# main.net
KiCad netlist of a schematic drawn in Altium Designer
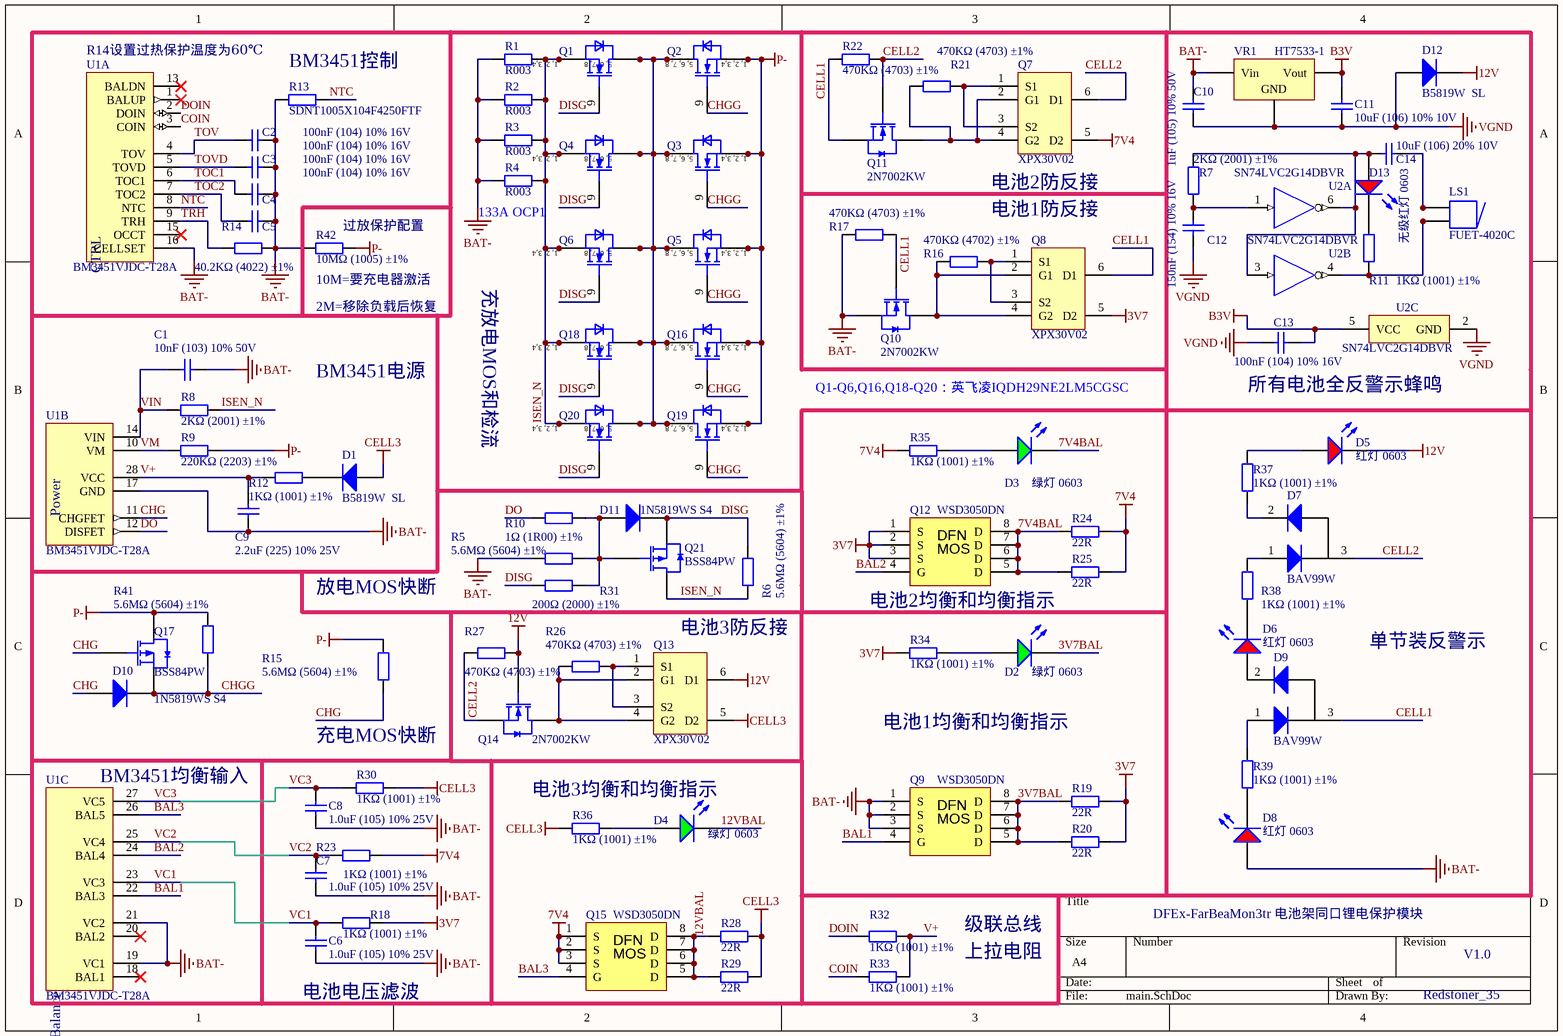
[diagram p0: main.SchDoc]

(export (version "E")
  (design (tool "Eeschema 10.0.6"))
  (components
    (comp (ref "C1")
      (value "10nF (103) 10% 50V")
      (footprint "0402_C")
      (description "贴片电容")
      (libsource (lib "Miscellaneous Devices LC") (part "0402 10nF (103) 10% 50V"))
    )
    (comp (ref "C2")
      (value "100nF (104) 10% 16V")
      (footprint "0402_C")
      (description "贴片电容")
      (libsource (lib "Miscellaneous Devices LC") (part "0402 100nF (104) 10% 16V"))
    )
    (comp (ref "C3")
      (value "100nF (104) 10% 16V")
      (footprint "0402_C")
      (description "贴片电容")
      (libsource (lib "Miscellaneous Devices LC") (part "0402 100nF (104) 10% 16V"))
    )
    (comp (ref "C4")
      (value "100nF (104) 10% 16V")
      (footprint "0402_C")
      (description "贴片电容")
      (libsource (lib "Miscellaneous Devices LC") (part "0402 100nF (104) 10% 16V"))
    )
    (comp (ref "C5")
      (value "100nF (104) 10% 16V")
      (footprint "0402_C")
      (description "贴片电容")
      (libsource (lib "Miscellaneous Devices LC") (part "0402 100nF (104) 10% 16V"))
    )
    (comp (ref "C6")
      (value "1.0uF (105) 10% 25V")
      (footprint "0402_C")
      (description "贴片电容")
      (libsource (lib "Miscellaneous Devices LC") (part "0402 1.0uF (105) 10% 25V"))
    )
    (comp (ref "C7")
      (value "1.0uF (105) 10% 25V")
      (footprint "0402_C")
      (description "贴片电容")
      (libsource (lib "Miscellaneous Devices LC") (part "0402 1.0uF (105) 10% 25V"))
    )
    (comp (ref "C8")
      (value "1.0uF (105) 10% 25V")
      (footprint "0402_C")
      (description "贴片电容")
      (libsource (lib "Miscellaneous Devices LC") (part "0402 1.0uF (105) 10% 25V"))
    )
    (comp (ref "C9")
      (value "2.2uF (225) 10% 25V")
      (footprint "0402_C")
      (description "贴片电容")
      (libsource (lib "Miscellaneous Devices LC") (part "0402 2.2nF (222) 10% 50V"))
    )
    (comp (ref "C10")
      (value "1uF (105) 10% 50V")
      (footprint "0603_C")
      (description "贴片电容")
      (libsource (lib "Miscellaneous Devices LC") (part "0603 1uF (105) 10% 50V"))
    )
    (comp (ref "C11")
      (value "10uF (106) 10% 10V")
      (footprint "0603_C")
      (description "贴片电容")
      (libsource (lib "Miscellaneous Devices LC") (part "0603 10uF (106) 10% 10V"))
    )
    (comp (ref "C12")
      (value "150nF (154) 10% 16V")
      (footprint "0402_C")
      (description "贴片电容")
      (libsource (lib "Miscellaneous Devices LC") (part "0402 100nF (104) 10% 16V"))
    )
    (comp (ref "C13")
      (value "100nF (104) 10% 16V")
      (footprint "0402_C")
      (description "贴片电容")
      (libsource (lib "Miscellaneous Devices LC") (part "0402 100nF (104) 10% 16V"))
    )
    (comp (ref "C14")
      (value "10uF (106) 20% 10V")
      (footprint "0402_C")
      (description "贴片电容")
      (libsource (lib "Miscellaneous Devices LC") (part "0402 10uF (106) 20% 6.3V"))
    )
    (comp (ref "D1")
      (value "B5819W  SL")
      (footprint "SOD-123")
      (description "肖特基二极管")
      (libsource (lib "Miscellaneous Devices LC") (part "SOD-123 B5819W  SL"))
    )
    (comp (ref "D2")
      (value "绿灯 0603")
      (footprint "0603_LED_S1")
      (description "发光二极管")
      (libsource (lib "Miscellaneous Devices LC") (part "0603 绿灯"))
    )
    (comp (ref "D3")
      (value "绿灯 0603")
      (footprint "0603_LED_S1")
      (description "发光二极管")
      (libsource (lib "Miscellaneous Devices LC") (part "0603 绿灯"))
    )
    (comp (ref "D4")
      (value "绿灯 0603")
      (footprint "0603_LED_S1")
      (description "发光二极管")
      (libsource (lib "Miscellaneous Devices LC") (part "0603 绿灯"))
    )
    (comp (ref "D5")
      (value "红灯 0603")
      (footprint "0603_LED_S1")
      (description "发光二极管")
      (libsource (lib "Miscellaneous Devices LC") (part "0603 红灯"))
    )
    (comp (ref "D6")
      (value "红灯 0603")
      (footprint "0603_LED_S1")
      (description "发光二极管")
      (libsource (lib "Miscellaneous Devices LC") (part "0603 红灯"))
    )
    (comp (ref "D7")
      (value "BAV99W")
      (footprint "SC70-3")
      (description "开关二极管")
      (libsource (lib "Miscellaneous Devices LC") (part "SOT-23 BAV99 A7W"))
    )
    (comp (ref "D8")
      (value "红灯 0603")
      (footprint "0603_LED_S1")
      (description "发光二极管")
      (libsource (lib "Miscellaneous Devices LC") (part "0603 红灯"))
    )
    (comp (ref "D9")
      (value "BAV99W")
      (footprint "SC70-3")
      (description "开关二极管")
      (libsource (lib "Miscellaneous Devices LC") (part "SOT-23 BAV99 A7W"))
    )
    (comp (ref "D10")
      (value "1N5819WS S4")
      (footprint "SOD-323")
      (description "二极管")
      (libsource (lib "Miscellaneous Devices LC") (part "SOD-323 1N4148WS T4"))
    )
    (comp (ref "D11")
      (value "1N5819WS S4")
      (footprint "SOD-323")
      (description "二极管")
      (libsource (lib "Miscellaneous Devices LC") (part "SOD-323 1N4148WS T4"))
    )
    (comp (ref "D12")
      (value "B5819W  SL")
      (footprint "SOD-123")
      (description "肖特基二极管")
      (libsource (lib "Miscellaneous Devices LC") (part "SOD-123 B5819W  SL"))
    )
    (comp (ref "D13")
      (value "无级红灯 0603")
      (footprint "0603_LED_S1")
      (description "发光二极管")
      (libsource (lib "Miscellaneous Devices LC") (part "0603 红灯"))
    )
    (comp (ref "LS1")
      (value "FUET-4020C")
      (footprint "FUET-4020C")
      (description "福声科技有限公司侧发声电磁式蜂鸣器，4*4*2mm尺寸")
      (fields (field (name "PUBLISHER") "Altium Limited"))
      (libsource (lib "Miscellaneous Devices") (part "Buzzer"))
    )
    (comp (ref "Q1")
      (value "IQDH29NE2LM5CGSC")
      (footprint "IFX-PG-WHTFN-9-2-V")
      (fields (field (name "MANUFACTURER") "Infineon Technologies"))
      (libsource (lib "custom") (part "IQDH29NE2LM5CGSC"))
    )
    (comp (ref "Q2")
      (value "IQDH29NE2LM5CGSC")
      (footprint "IFX-PG-WHTFN-9-2-V")
      (fields (field (name "MANUFACTURER") "Infineon Technologies"))
      (libsource (lib "custom") (part "IQDH29NE2LM5CGSC"))
    )
    (comp (ref "Q3")
      (value "IQDH29NE2LM5CGSC")
      (footprint "IFX-PG-WHTFN-9-2-V")
      (fields (field (name "MANUFACTURER") "Infineon Technologies"))
      (libsource (lib "custom") (part "IQDH29NE2LM5CGSC"))
    )
    (comp (ref "Q4")
      (value "IQDH29NE2LM5CGSC")
      (footprint "IFX-PG-WHTFN-9-2-V")
      (fields (field (name "MANUFACTURER") "Infineon Technologies"))
      (libsource (lib "custom") (part "IQDH29NE2LM5CGSC"))
    )
    (comp (ref "Q5")
      (value "IQDH29NE2LM5CGSC")
      (footprint "IFX-PG-WHTFN-9-2-V")
      (fields (field (name "MANUFACTURER") "Infineon Technologies"))
      (libsource (lib "custom") (part "IQDH29NE2LM5CGSC"))
    )
    (comp (ref "Q6")
      (value "IQDH29NE2LM5CGSC")
      (footprint "IFX-PG-WHTFN-9-2-V")
      (fields (field (name "MANUFACTURER") "Infineon Technologies"))
      (libsource (lib "custom") (part "IQDH29NE2LM5CGSC"))
    )
    (comp (ref "Q7")
      (value "XPX30V02")
      (footprint "EDFN3x3")
      (description "双N沟道MOSFET, DFN3x3 30V 40A 10mΩ")
      (libsource (lib "custom") (part "XPX10H03RX"))
    )
    (comp (ref "Q8")
      (value "XPX30V02")
      (footprint "EDFN3x3")
      (description "双N沟道MOSFET, DFN3x3 30V 40A 10mΩ")
      (libsource (lib "custom") (part "XPX10H03RX"))
    )
    (comp (ref "Q9")
      (value "WSD3050DN")
      (footprint "DFN-8_L3.0-W3.0-P0.65-BL")
      (description "PDFN3x3 20V 50A 5.8mΩ N-Ch MOSFET")
      (libsource (lib "custom") (part "SON/DFN5x6 MOS"))
    )
    (comp (ref "Q10")
      (value "2N7002KW")
      (footprint "SC70-3")
      (description "单N沟道MOSFET(场效应管)")
      (libsource (lib "Miscellaneous Devices LC") (part "2N7002 7002"))
    )
    (comp (ref "Q11")
      (value "2N7002KW")
      (footprint "SC70-3")
      (description "单N沟道MOSFET(场效应管)")
      (libsource (lib "Miscellaneous Devices LC") (part "2N7002 7002"))
    )
    (comp (ref "Q12")
      (value "WSD3050DN")
      (footprint "DFN-8_L3.0-W3.0-P0.65-BL")
      (description "PDFN3x3 20V 50A 5.8mΩ N-Ch MOSFET")
      (libsource (lib "custom") (part "SON/DFN5x6 MOS"))
    )
    (comp (ref "Q13")
      (value "XPX30V02")
      (footprint "EDFN3x3")
      (description "双N沟道MOSFET, DFN3x3 30V 40A 10mΩ")
      (libsource (lib "custom") (part "XPX10H03RX"))
    )
    (comp (ref "Q14")
      (value "2N7002KW")
      (footprint "SC70-3")
      (description "单N沟道MOSFET(场效应管)")
      (libsource (lib "Miscellaneous Devices LC") (part "2N7002 7002"))
    )
    (comp (ref "Q15")
      (value "WSD3050DN")
      (footprint "DFN-8_L3.0-W3.0-P0.65-BL")
      (description "PDFN3x3 20V 50A 5.8mΩ N-Ch MOSFET")
      (libsource (lib "custom") (part "SON/DFN5x6 MOS"))
    )
    (comp (ref "Q16")
      (value "IQDH29NE2LM5CGSC")
      (footprint "IFX-PG-WHTFN-9-2-V")
      (fields (field (name "MANUFACTURER") "Infineon Technologies"))
      (libsource (lib "custom") (part "IQDH29NE2LM5CGSC"))
    )
    (comp (ref "Q17")
      (value "BSS84PW")
      (footprint "SC70-3")
      (description "MOS(场效应管)")
      (libsource (lib "Miscellaneous Devices LC") (part "SI2301CDS-T1-GE3"))
    )
    (comp (ref "Q18")
      (value "IQDH29NE2LM5CGSC")
      (footprint "IFX-PG-WHTFN-9-2-V")
      (fields (field (name "MANUFACTURER") "Infineon Technologies"))
      (libsource (lib "custom") (part "IQDH29NE2LM5CGSC"))
    )
    (comp (ref "Q19")
      (value "IQDH29NE2LM5CGSC")
      (footprint "IFX-PG-WHTFN-9-2-V")
      (fields (field (name "MANUFACTURER") "Infineon Technologies"))
      (libsource (lib "custom") (part "IQDH29NE2LM5CGSC"))
    )
    (comp (ref "Q20")
      (value "IQDH29NE2LM5CGSC")
      (footprint "IFX-PG-WHTFN-9-2-V")
      (fields (field (name "MANUFACTURER") "Infineon Technologies"))
      (libsource (lib "custom") (part "IQDH29NE2LM5CGSC"))
    )
    (comp (ref "Q21")
      (value "BSS84PW")
      (footprint "SC70-3")
      (description "MOS(场效应管)")
      (libsource (lib "Miscellaneous Devices LC") (part "SI2301CDS-T1-GE3"))
    )
    (comp (ref "R1")
      (value "R003")
      (footprint "2512")
      (description "2512尺寸 3W 3mΩ ±1% 合金检流电阻")
      (fields (field (name "PUBLISHER") "Altium Limited"))
      (libsource (lib "山猫的集成库20190318") (part "Res"))
    )
    (comp (ref "R2")
      (value "R003")
      (footprint "2512")
      (description "2512尺寸 3W 3mΩ ±1% 合金检流电阻")
      (fields (field (name "PUBLISHER") "Altium Limited"))
      (libsource (lib "山猫的集成库20190318") (part "Res"))
    )
    (comp (ref "R3")
      (value "R003")
      (footprint "2512")
      (description "2512尺寸 3W 3mΩ ±1% 合金检流电阻")
      (fields (field (name "PUBLISHER") "Altium Limited"))
      (libsource (lib "山猫的集成库20190318") (part "Res"))
    )
    (comp (ref "R4")
      (value "R003")
      (footprint "2512")
      (description "2512尺寸 3W 3mΩ ±1% 合金检流电阻")
      (fields (field (name "PUBLISHER") "Altium Limited"))
      (libsource (lib "山猫的集成库20190318") (part "Res"))
    )
    (comp (ref "R5")
      (value "5.6MΩ (5604) ±1%")
      (footprint "0402_R")
      (description "贴片电阻")
      (libsource (lib "Miscellaneous Devices LC") (part "0402 1MΩ (1004) 1%"))
    )
    (comp (ref "R6")
      (value "5.6MΩ (5604) ±1%")
      (footprint "0402_R")
      (description "贴片电阻")
      (libsource (lib "") (part "0402 1MΩ (1004) 1%_1"))
    )
    (comp (ref "R7")
      (value "2KΩ (2001) ±1%")
      (footprint "0402_R")
      (description "贴片电阻")
      (libsource (lib "") (part "0402 1KΩ (1001) 1%_1"))
    )
    (comp (ref "R8")
      (value "2KΩ (2001) ±1%")
      (footprint "0402_R")
      (description "贴片电阻")
      (libsource (lib "Miscellaneous Devices LC") (part "0402 2KΩ (2001) 1%"))
    )
    (comp (ref "R9")
      (value "220KΩ (2203) ±1%")
      (footprint "0402_R")
      (description "贴片电阻")
      (libsource (lib "Miscellaneous Devices LC") (part "0402 220KΩ (2203) 1%"))
    )
    (comp (ref "R10")
      (value "1Ω (1R00) ±1%")
      (footprint "0402_R")
      (description "贴片电阻")
      (libsource (lib "Miscellaneous Devices LC") (part "0402 1Ω (1R00) 1%"))
    )
    (comp (ref "R11")
      (value "1KΩ (1001) ±1%")
      (footprint "0402_R")
      (description "贴片电阻")
      (libsource (lib "") (part "0402 1KΩ (1001) 1%_1"))
    )
    (comp (ref "R12")
      (value "1KΩ (1001) ±1%")
      (footprint "0805_R")
      (description "贴片电阻")
      (libsource (lib "Miscellaneous Devices LC") (part "0805 1KΩ (1001) 1%"))
    )
    (comp (ref "R13")
      (value "SDNT1005X104F4250FTF")
      (footprint "0402_R")
      (description "贴片NTC热敏电阻 100KΩ (1003) ±1% B4250")
      (libsource (lib "Miscellaneous Devices LC") (part "0402 100KΩ (1003) 1%"))
    )
    (comp (ref "R14")
      (value "40.2KΩ (4022) ±1%")
      (footprint "0402_R")
      (description "贴片电阻")
      (libsource (lib "Miscellaneous Devices LC") (part "0402 56KΩ (5602) 1%"))
    )
    (comp (ref "R15")
      (value "5.6MΩ (5604) ±1%")
      (footprint "0402_R")
      (description "贴片电阻")
      (libsource (lib "") (part "0402 1MΩ (1004) 1%_1"))
    )
    (comp (ref "R16")
      (value "470KΩ (4702) ±1%")
      (footprint "0402_R")
      (description "贴片电阻")
      (libsource (lib "Miscellaneous Devices LC") (part "0402 20KΩ (2002) 1%"))
    )
    (comp (ref "R17")
      (value "470KΩ (4703) ±1%")
      (footprint "0402_R")
      (description "贴片电阻")
      (libsource (lib "Miscellaneous Devices LC") (part "0402 470KΩ (4703) 1%"))
    )
    (comp (ref "R18")
      (value "1KΩ (1001) ±1%")
      (footprint "0402_R")
      (description "贴片电阻")
      (libsource (lib "Miscellaneous Devices LC") (part "0402 1KΩ (1001) 1%"))
    )
    (comp (ref "R19")
      (value "22R")
      (footprint "1210R")
      (description "Resistor")
      (fields (field (name "PUBLISHER") "Altium Limited"))
      (libsource (lib "山猫的集成库20190318") (part "Res"))
    )
    (comp (ref "R20")
      (value "22R")
      (footprint "1210R")
      (description "Resistor")
      (fields (field (name "PUBLISHER") "Altium Limited"))
      (libsource (lib "山猫的集成库20190318") (part "Res"))
    )
    (comp (ref "R21")
      (value "470KΩ (4703) ±1%")
      (footprint "0402_R")
      (description "贴片电阻")
      (libsource (lib "Miscellaneous Devices LC") (part "0402 470KΩ (4703) 1%"))
    )
    (comp (ref "R22")
      (value "470KΩ (4703) ±1%")
      (footprint "0402_R")
      (description "贴片电阻")
      (libsource (lib "Miscellaneous Devices LC") (part "0402 470KΩ (4703) 1%"))
    )
    (comp (ref "R23")
      (value "1KΩ (1001) ±1%")
      (footprint "0402_R")
      (description "贴片电阻")
      (libsource (lib "Miscellaneous Devices LC") (part "0402 1KΩ (1001) 1%"))
    )
    (comp (ref "R24")
      (value "22R")
      (footprint "1210R")
      (description "Resistor")
      (fields (field (name "PUBLISHER") "Altium Limited"))
      (libsource (lib "山猫的集成库20190318") (part "Res"))
    )
    (comp (ref "R25")
      (value "22R")
      (footprint "1210R")
      (description "Resistor")
      (fields (field (name "PUBLISHER") "Altium Limited"))
      (libsource (lib "山猫的集成库20190318") (part "Res"))
    )
    (comp (ref "R26")
      (value "470KΩ (4703) ±1%")
      (footprint "0402_R")
      (description "贴片电阻")
      (libsource (lib "Miscellaneous Devices LC") (part "0402 470KΩ (4703) 1%"))
    )
    (comp (ref "R27")
      (value "470KΩ (4703) ±1%")
      (footprint "0402_R")
      (description "贴片电阻")
      (libsource (lib "Miscellaneous Devices LC") (part "0402 470KΩ (4703) 1%"))
    )
    (comp (ref "R28")
      (value "22R")
      (footprint "1210R")
      (description "Resistor")
      (fields (field (name "PUBLISHER") "Altium Limited"))
      (libsource (lib "山猫的集成库20190318") (part "Res"))
    )
    (comp (ref "R29")
      (value "22R")
      (footprint "1210R")
      (description "Resistor")
      (fields (field (name "PUBLISHER") "Altium Limited"))
      (libsource (lib "山猫的集成库20190318") (part "Res"))
    )
    (comp (ref "R30")
      (value "1KΩ (1001) ±1%")
      (footprint "0402_R")
      (description "贴片电阻")
      (libsource (lib "Miscellaneous Devices LC") (part "0402 1KΩ (1001) 1%"))
    )
    (comp (ref "R31")
      (value "200Ω (2000) ±1%")
      (footprint "0402_R")
      (description "贴片电阻")
      (libsource (lib "Miscellaneous Devices LC") (part "0402 200Ω (2000) 1%"))
    )
    (comp (ref "R32")
      (value "1KΩ (1001) ±1%")
      (footprint "0402_R")
      (description "贴片电阻")
      (libsource (lib "Miscellaneous Devices LC") (part "0402 1KΩ (1001) 1%"))
    )
    (comp (ref "R33")
      (value "1KΩ (1001) ±1%")
      (footprint "0402_R")
      (description "贴片电阻")
      (libsource (lib "Miscellaneous Devices LC") (part "0402 1KΩ (1001) 1%"))
    )
    (comp (ref "R34")
      (value "1KΩ (1001) ±1%")
      (footprint "0402_R")
      (description "贴片电阻")
      (libsource (lib "Miscellaneous Devices LC") (part "0402 1KΩ (1001) 1%"))
    )
    (comp (ref "R35")
      (value "1KΩ (1001) ±1%")
      (footprint "0402_R")
      (description "贴片电阻")
      (libsource (lib "Miscellaneous Devices LC") (part "0402 1KΩ (1001) 1%"))
    )
    (comp (ref "R36")
      (value "1KΩ (1001) ±1%")
      (footprint "0402_R")
      (description "贴片电阻")
      (libsource (lib "Miscellaneous Devices LC") (part "0402 1KΩ (1001) 1%"))
    )
    (comp (ref "R37")
      (value "1KΩ (1001) ±1%")
      (footprint "0402_R")
      (description "贴片电阻")
      (libsource (lib "") (part "0402 1KΩ (1001) 1%_1"))
    )
    (comp (ref "R38")
      (value "1KΩ (1001) ±1%")
      (footprint "0402_R")
      (description "贴片电阻")
      (libsource (lib "") (part "0402 1KΩ (1001) 1%_1"))
    )
    (comp (ref "R39")
      (value "1KΩ (1001) ±1%")
      (footprint "0402_R")
      (description "贴片电阻")
      (libsource (lib "") (part "0402 1KΩ (1001) 1%_1"))
    )
    (comp (ref "R41")
      (value "5.6MΩ (5604) ±1%")
      (footprint "0402_R")
      (description "贴片电阻")
      (libsource (lib "") (part "0402 1MΩ (1004) 1%_1"))
    )
    (comp (ref "R42")
      (value "10MΩ (1005) ±1%")
      (footprint "0402_R")
      (description "贴片电阻")
      (libsource (lib "Miscellaneous Devices LC") (part "0402 10MΩ (1005) 1%"))
    )
    (comp (ref "U1")
      (value "BM3451VJDC-T28A")
      (footprint "TSSOP28-BM3451")
      (description "2-5串全功能锂电池保护IC，支持级联功能")
      (libsource (lib "custom") (part "BM3451-T28A"))
    )
    (comp (ref "U2")
      (value "SN74LVC2G14DBVR")
      (footprint "DBV0006A_N")
      (description "Dual Schmitt-Trigger Inverter, DBV0006A, LARGE T&R")
      (fields
        (field (name "GENERIC PART NUMBER") "SN74LVC2G14")
        (field (name "MANUFACTURER") "Texas Instruments")
      )
      (libsource (lib "TI_Logic_Little_Logic") (part "SN74LVC2G14DBVR"))
    )
    (comp (ref "VR1")
      (value "HT7533-1")
      (footprint "SOT-89(SOT-89-3)")
      (description "低压差线性稳压(LDO)")
      (libsource (lib "Miscellaneous Devices LC") (part "SOT-89 HT7533-1"))
    )
  )
  (nets
    (net (code "1") (name "/3V7BAL") (class "Default")
      (node (ref "D2") (pin "K") (pinfunction "K_K") (pintype "passive"))
      (node (ref "Q9") (pin "5") (pinfunction "D_5") (pintype "passive"))
      (node (ref "Q9") (pin "6") (pinfunction "D_6") (pintype "passive"))
      (node (ref "Q9") (pin "7") (pinfunction "D_7") (pintype "passive"))
      (node (ref "Q9") (pin "8") (pinfunction "D_8") (pintype "passive"))
      (node (ref "R19") (pin "2") (pinfunction "2_2") (pintype "passive"))
      (node (ref "R20") (pin "2") (pinfunction "2_2") (pintype "passive"))
    )
    (net (code "2") (name "/7V4BAL") (class "Default")
      (node (ref "D3") (pin "K") (pinfunction "K_K") (pintype "passive"))
      (node (ref "Q12") (pin "5") (pinfunction "D_5") (pintype "passive"))
      (node (ref "Q12") (pin "6") (pinfunction "D_6") (pintype "passive"))
      (node (ref "Q12") (pin "7") (pinfunction "D_7") (pintype "passive"))
      (node (ref "Q12") (pin "8") (pinfunction "D_8") (pintype "passive"))
      (node (ref "R24") (pin "2") (pinfunction "2_2") (pintype "passive"))
      (node (ref "R25") (pin "2") (pinfunction "2_2") (pintype "passive"))
    )
    (net (code "3") (name "/12VBAL") (class "Default")
      (node (ref "D4") (pin "K") (pinfunction "K_K") (pintype "passive"))
      (node (ref "Q15") (pin "5") (pinfunction "D_5") (pintype "passive"))
      (node (ref "Q15") (pin "6") (pinfunction "D_6") (pintype "passive"))
      (node (ref "Q15") (pin "7") (pinfunction "D_7") (pintype "passive"))
      (node (ref "Q15") (pin "8") (pinfunction "D_8") (pintype "passive"))
      (node (ref "R28") (pin "2") (pinfunction "2_2") (pintype "passive"))
      (node (ref "R29") (pin "2") (pinfunction "2_2") (pintype "passive"))
    )
    (net (code "4") (name "/BAL1") (class "Default")
      (node (ref "Q9") (pin "4") (pinfunction "G_4") (pintype "passive"))
      (node (ref "U1") (pin "22") (pinfunction "BAL3_22") (pintype "power_in"))
    )
    (net (code "5") (name "/BAL2") (class "Default")
      (node (ref "Q12") (pin "4") (pinfunction "G_4") (pintype "passive"))
      (node (ref "U1") (pin "24") (pinfunction "BAL4_24") (pintype "power_in"))
    )
    (net (code "6") (name "/BAL3") (class "Default")
      (node (ref "Q15") (pin "4") (pinfunction "G_4") (pintype "passive"))
      (node (ref "U1") (pin "26") (pinfunction "BAL5_26") (pintype "power_in"))
    )
    (net (code "7") (name "/CELL1") (class "Default")
      (node (ref "D9") (pin "3") (pinfunction "K_3") (pintype "passive"))
      (node (ref "Q10") (pin "1") (pinfunction "G_1") (pintype "passive"))
      (node (ref "Q11") (pin "2") (pinfunction "S_2") (pintype "passive"))
      (node (ref "Q8") (pin "6") (pinfunction "D1_6") (pintype "passive"))
      (node (ref "R17") (pin "2") (pinfunction "2_2") (pintype "passive"))
      (node (ref "R22") (pin "1") (pinfunction "1_1") (pintype "passive"))
    )
    (net (code "8") (name "/CELL2") (class "Default")
      (node (ref "D7") (pin "3") (pinfunction "K_3") (pintype "passive"))
      (node (ref "Q11") (pin "1") (pinfunction "G_1") (pintype "passive"))
      (node (ref "Q14") (pin "2") (pinfunction "S_2") (pintype "passive"))
      (node (ref "Q7") (pin "6") (pinfunction "D1_6") (pintype "passive"))
      (node (ref "R22") (pin "2") (pinfunction "2_2") (pintype "passive"))
      (node (ref "R27") (pin "1") (pinfunction "1_1") (pintype "passive"))
    )
    (net (code "9") (name "/CHG") (class "Default")
      (node (ref "D10") (pin "1") (pinfunction "A_1") (pintype "passive"))
      (node (ref "Q17") (pin "1") (pinfunction "G_1") (pintype "passive"))
      (node (ref "R15") (pin "1") (pinfunction "1_1") (pintype "passive"))
      (node (ref "U1") (pin "11") (pinfunction "CHGFET_11") (pintype "output"))
    )
    (net (code "10") (name "/CHGG") (class "Default")
      (node (ref "D10") (pin "2") (pinfunction "K_2") (pintype "passive"))
      (node (ref "Q16") (pin "9") (pinfunction "GATE_9") (pintype "passive"))
      (node (ref "Q17") (pin "2") (pinfunction "S_2") (pintype "passive"))
      (node (ref "Q19") (pin "9") (pinfunction "GATE_9") (pintype "passive"))
      (node (ref "Q2") (pin "9") (pinfunction "GATE_9") (pintype "passive"))
      (node (ref "Q3") (pin "9") (pinfunction "GATE_9") (pintype "passive"))
      (node (ref "Q5") (pin "9") (pinfunction "GATE_9") (pintype "passive"))
      (node (ref "R41") (pin "1") (pinfunction "1_1") (pintype "passive"))
    )
    (net (code "11") (name "/COIN") (class "Default")
      (node (ref "R33") (pin "1") (pinfunction "1_1") (pintype "passive"))
      (node (ref "U1") (pin "3") (pinfunction "COIN_3") (pintype "bidirectional"))
    )
    (net (code "12") (name "/DISG") (class "Default")
      (node (ref "D11") (pin "2") (pinfunction "K_2") (pintype "passive"))
      (node (ref "Q1") (pin "9") (pinfunction "GATE_9") (pintype "passive"))
      (node (ref "Q18") (pin "9") (pinfunction "GATE_9") (pintype "passive"))
      (node (ref "Q20") (pin "9") (pinfunction "GATE_9") (pintype "passive"))
      (node (ref "Q21") (pin "2") (pinfunction "S_2") (pintype "passive"))
      (node (ref "Q4") (pin "9") (pinfunction "GATE_9") (pintype "passive"))
      (node (ref "Q6") (pin "9") (pinfunction "GATE_9") (pintype "passive"))
      (node (ref "R31") (pin "1") (pinfunction "1_1") (pintype "passive"))
      (node (ref "R6") (pin "2") (pinfunction "2_2") (pintype "passive"))
    )
    (net (code "13") (name "/DO") (class "Default")
      (node (ref "R10") (pin "1") (pinfunction "1_1") (pintype "passive"))
      (node (ref "U1") (pin "12") (pinfunction "DISFET_12") (pintype "output"))
    )
    (net (code "14") (name "/DOIN") (class "Default")
      (node (ref "R32") (pin "1") (pinfunction "1_1") (pintype "passive"))
      (node (ref "U1") (pin "2") (pinfunction "DOIN_2") (pintype "bidirectional"))
    )
    (net (code "15") (name "/ISEN_N") (class "Default")
      (node (ref "Q1") (pin "1") (pinfunction "SOURCE1_1") (pintype "passive"))
      (node (ref "Q1") (pin "2") (pinfunction "SOURCE2_2") (pintype "passive"))
      (node (ref "Q1") (pin "3") (pinfunction "SOURCE3_3") (pintype "passive"))
      (node (ref "Q1") (pin "4") (pinfunction "SOURCE4_4") (pintype "passive"))
      (node (ref "Q18") (pin "1") (pinfunction "SOURCE1_1") (pintype "passive"))
      (node (ref "Q18") (pin "2") (pinfunction "SOURCE2_2") (pintype "passive"))
      (node (ref "Q18") (pin "3") (pinfunction "SOURCE3_3") (pintype "passive"))
      (node (ref "Q18") (pin "4") (pinfunction "SOURCE4_4") (pintype "passive"))
      (node (ref "Q20") (pin "1") (pinfunction "SOURCE1_1") (pintype "passive"))
      (node (ref "Q20") (pin "2") (pinfunction "SOURCE2_2") (pintype "passive"))
      (node (ref "Q20") (pin "3") (pinfunction "SOURCE3_3") (pintype "passive"))
      (node (ref "Q20") (pin "4") (pinfunction "SOURCE4_4") (pintype "passive"))
      (node (ref "Q21") (pin "3") (pinfunction "D_3") (pintype "passive"))
      (node (ref "Q4") (pin "1") (pinfunction "SOURCE1_1") (pintype "passive"))
      (node (ref "Q4") (pin "2") (pinfunction "SOURCE2_2") (pintype "passive"))
      (node (ref "Q4") (pin "3") (pinfunction "SOURCE3_3") (pintype "passive"))
      (node (ref "Q4") (pin "4") (pinfunction "SOURCE4_4") (pintype "passive"))
      (node (ref "Q6") (pin "1") (pinfunction "SOURCE1_1") (pintype "passive"))
      (node (ref "Q6") (pin "2") (pinfunction "SOURCE2_2") (pintype "passive"))
      (node (ref "Q6") (pin "3") (pinfunction "SOURCE3_3") (pintype "passive"))
      (node (ref "Q6") (pin "4") (pinfunction "SOURCE4_4") (pintype "passive"))
      (node (ref "R1") (pin "1") (pinfunction "1_1") (pintype "passive"))
      (node (ref "R2") (pin "1") (pinfunction "1_1") (pintype "passive"))
      (node (ref "R3") (pin "1") (pinfunction "1_1") (pintype "passive"))
      (node (ref "R4") (pin "1") (pinfunction "1_1") (pintype "passive"))
      (node (ref "R6") (pin "1") (pinfunction "1_1") (pintype "passive"))
      (node (ref "R8") (pin "2") (pinfunction "2_2") (pintype "passive"))
    )
    (net (code "16") (name "/NTC") (class "Default")
      (node (ref "R13") (pin "1") (pinfunction "1_1") (pintype "passive"))
      (node (ref "U1") (pin "8") (pinfunction "NTC_8") (pintype "passive"))
    )
    (net (code "17") (name "/TOC1") (class "Default")
      (node (ref "C4") (pin "1") (pinfunction "1_1") (pintype "passive"))
      (node (ref "U1") (pin "6") (pinfunction "TOC1_6") (pintype "passive"))
    )
    (net (code "18") (name "/TOC2") (class "Default")
      (node (ref "C5") (pin "1") (pinfunction "1_1") (pintype "passive"))
      (node (ref "U1") (pin "7") (pinfunction "TOC2_7") (pintype "passive"))
    )
    (net (code "19") (name "/TOV") (class "Default")
      (node (ref "C2") (pin "1") (pinfunction "1_1") (pintype "passive"))
      (node (ref "U1") (pin "4") (pinfunction "TOV_4") (pintype "passive"))
    )
    (net (code "20") (name "/TOVD") (class "Default")
      (node (ref "C3") (pin "1") (pinfunction "1_1") (pintype "passive"))
      (node (ref "U1") (pin "5") (pinfunction "TOVD_5") (pintype "passive"))
    )
    (net (code "21") (name "/TRH") (class "Default")
      (node (ref "R14") (pin "1") (pinfunction "1_1") (pintype "passive"))
      (node (ref "U1") (pin "9") (pinfunction "TRH_9") (pintype "passive"))
    )
    (net (code "22") (name "/V+") (class "Default")
      (node (ref "C9") (pin "2") (pinfunction "2_2") (pintype "passive"))
      (node (ref "R12") (pin "1") (pinfunction "1_1") (pintype "passive"))
      (node (ref "R32") (pin "2") (pinfunction "2_2") (pintype "passive"))
      (node (ref "R33") (pin "2") (pinfunction "2_2") (pintype "passive"))
      (node (ref "U1") (pin "28") (pinfunction "VCC_28") (pintype "power_in"))
    )
    (net (code "23") (name "/VC1") (class "Default")
      (node (ref "C6") (pin "2") (pinfunction "2_2") (pintype "passive"))
      (node (ref "R18") (pin "1") (pinfunction "1_1") (pintype "passive"))
      (node (ref "U1") (pin "23") (pinfunction "VC3_23") (pintype "power_in"))
    )
    (net (code "24") (name "/VC2") (class "Default")
      (node (ref "C7") (pin "2") (pinfunction "2_2") (pintype "passive"))
      (node (ref "R23") (pin "1") (pinfunction "1_1") (pintype "passive"))
      (node (ref "U1") (pin "25") (pinfunction "VC4_25") (pintype "power_in"))
    )
    (net (code "25") (name "/VC3") (class "Default")
      (node (ref "C8") (pin "2") (pinfunction "2_2") (pintype "passive"))
      (node (ref "R30") (pin "1") (pinfunction "1_1") (pintype "passive"))
      (node (ref "U1") (pin "27") (pinfunction "VC5_27") (pintype "power_in"))
    )
    (net (code "26") (name "/VIN") (class "Default")
      (node (ref "C1") (pin "1") (pinfunction "1_1") (pintype "passive"))
      (node (ref "R8") (pin "1") (pinfunction "1_1") (pintype "passive"))
      (node (ref "U1") (pin "14") (pinfunction "VIN_14") (pintype "power_in"))
    )
    (net (code "27") (name "/VM") (class "Default")
      (node (ref "R9") (pin "1") (pinfunction "1_1") (pintype "passive"))
      (node (ref "U1") (pin "10") (pinfunction "VM_10") (pintype "passive"))
    )
    (net (code "28") (name "3V7") (class "Default")
      (node (ref "Q12") (pin "1") (pinfunction "S_1") (pintype "passive"))
      (node (ref "Q12") (pin "2") (pinfunction "S_2") (pintype "passive"))
      (node (ref "Q12") (pin "3") (pinfunction "S_3") (pintype "passive"))
      (node (ref "Q8") (pin "5") (pinfunction "D2_5") (pintype "passive"))
      (node (ref "R18") (pin "2") (pinfunction "2_2") (pintype "passive"))
      (node (ref "R19") (pin "1") (pinfunction "1_1") (pintype "passive"))
      (node (ref "R20") (pin "1") (pinfunction "1_1") (pintype "passive"))
      (node (ref "R34") (pin "1") (pinfunction "1_1") (pintype "passive"))
    )
    (net (code "29") (name "7V4") (class "Default")
      (node (ref "Q15") (pin "1") (pinfunction "S_1") (pintype "passive"))
      (node (ref "Q15") (pin "2") (pinfunction "S_2") (pintype "passive"))
      (node (ref "Q15") (pin "3") (pinfunction "S_3") (pintype "passive"))
      (node (ref "Q7") (pin "5") (pinfunction "D2_5") (pintype "passive"))
      (node (ref "R23") (pin "2") (pinfunction "2_2") (pintype "passive"))
      (node (ref "R24") (pin "1") (pinfunction "1_1") (pintype "passive"))
      (node (ref "R25") (pin "1") (pinfunction "1_1") (pintype "passive"))
      (node (ref "R35") (pin "1") (pinfunction "1_1") (pintype "passive"))
    )
    (net (code "30") (name "12V") (class "Default")
      (node (ref "D12") (pin "2") (pinfunction "K_2") (pintype "passive"))
      (node (ref "D5") (pin "K") (pinfunction "K_K") (pintype "passive"))
      (node (ref "Q13") (pin "6") (pinfunction "D1_6") (pintype "passive"))
      (node (ref "Q14") (pin "1") (pinfunction "G_1") (pintype "passive"))
      (node (ref "R27") (pin "2") (pinfunction "2_2") (pintype "passive"))
    )
    (net (code "31") (name "B3V") (class "Default")
      (node (ref "C11") (pin "2") (pinfunction "2_2") (pintype "passive"))
      (node (ref "C13") (pin "1") (pinfunction "1_1") (pintype "passive"))
      (node (ref "U2") (pin "5") (pinfunction "VCC_5") (pintype "power_in"))
      (node (ref "VR1") (pin "3") (pinfunction "Vout_3") (pintype "passive"))
    )
    (net (code "32") (name "BAT-") (class "Default")
      (node (ref "C1") (pin "2") (pinfunction "2_2") (pintype "passive"))
      (node (ref "C10") (pin "2") (pinfunction "2_2") (pintype "passive"))
      (node (ref "C2") (pin "2") (pinfunction "2_2") (pintype "passive"))
      (node (ref "C3") (pin "2") (pinfunction "2_2") (pintype "passive"))
      (node (ref "C4") (pin "2") (pinfunction "2_2") (pintype "passive"))
      (node (ref "C5") (pin "2") (pinfunction "2_2") (pintype "passive"))
      (node (ref "C6") (pin "1") (pinfunction "1_1") (pintype "passive"))
      (node (ref "C7") (pin "1") (pinfunction "1_1") (pintype "passive"))
      (node (ref "C8") (pin "1") (pinfunction "1_1") (pintype "passive"))
      (node (ref "C9") (pin "1") (pinfunction "1_1") (pintype "passive"))
      (node (ref "D8") (pin "A") (pinfunction "A_A") (pintype "passive"))
      (node (ref "Q10") (pin "2") (pinfunction "S_2") (pintype "passive"))
      (node (ref "Q9") (pin "1") (pinfunction "S_1") (pintype "passive"))
      (node (ref "Q9") (pin "2") (pinfunction "S_2") (pintype "passive"))
      (node (ref "Q9") (pin "3") (pinfunction "S_3") (pintype "passive"))
      (node (ref "R1") (pin "2") (pinfunction "2_2") (pintype "passive"))
      (node (ref "R13") (pin "2") (pinfunction "2_2") (pintype "passive"))
      (node (ref "R14") (pin "2") (pinfunction "2_2") (pintype "passive"))
      (node (ref "R17") (pin "1") (pinfunction "1_1") (pintype "passive"))
      (node (ref "R2") (pin "2") (pinfunction "2_2") (pintype "passive"))
      (node (ref "R3") (pin "2") (pinfunction "2_2") (pintype "passive"))
      (node (ref "R4") (pin "2") (pinfunction "2_2") (pintype "passive"))
      (node (ref "R42") (pin "1") (pinfunction "1_1") (pintype "passive"))
      (node (ref "R5") (pin "2") (pinfunction "2_2") (pintype "passive"))
      (node (ref "U1") (pin "16") (pinfunction "CELLSET_16") (pintype "passive"))
      (node (ref "U1") (pin "17") (pinfunction "GND_17") (pintype "passive"))
      (node (ref "U1") (pin "19") (pinfunction "VC1_19") (pintype "power_in"))
      (node (ref "U1") (pin "21") (pinfunction "VC2_21") (pintype "power_in"))
      (node (ref "VR1") (pin "2") (pinfunction "Vin_2") (pintype "passive"))
    )
    (net (code "33") (name "CELL3") (class "Default")
      (node (ref "D1") (pin "1") (pinfunction "A_1") (pintype "passive"))
      (node (ref "Q13") (pin "5") (pinfunction "D2_5") (pintype "passive"))
      (node (ref "R28") (pin "1") (pinfunction "1_1") (pintype "passive"))
      (node (ref "R29") (pin "1") (pinfunction "1_1") (pintype "passive"))
      (node (ref "R30") (pin "2") (pinfunction "2_2") (pintype "passive"))
      (node (ref "R36") (pin "1") (pinfunction "1_1") (pintype "passive"))
    )
    (net (code "34") (name "Net-(C14-Pad2)") (class "Default")
      (node (ref "C14") (pin "2") (pinfunction "2_2") (pintype "passive"))
      (node (ref "LS1") (pin "2") (pinfunction "2_2") (pintype "passive"))
      (node (ref "LS1") (pin "2A") (pinfunction "2A_2A") (pintype "passive"))
    )
    (net (code "35") (name "Net-(D1-K)") (class "Default")
      (node (ref "D1") (pin "2") (pinfunction "K_2") (pintype "passive"))
      (node (ref "R12") (pin "2") (pinfunction "2_2") (pintype "passive"))
    )
    (net (code "36") (name "Net-(D2-PadA)") (class "Default")
      (node (ref "D2") (pin "A") (pinfunction "A_A") (pintype "passive"))
      (node (ref "R34") (pin "2") (pinfunction "2_2") (pintype "passive"))
    )
    (net (code "37") (name "Net-(D3-PadA)") (class "Default")
      (node (ref "D3") (pin "A") (pinfunction "A_A") (pintype "passive"))
      (node (ref "R35") (pin "2") (pinfunction "2_2") (pintype "passive"))
    )
    (net (code "38") (name "Net-(D4-PadA)") (class "Default")
      (node (ref "D4") (pin "A") (pinfunction "A_A") (pintype "passive"))
      (node (ref "R36") (pin "2") (pinfunction "2_2") (pintype "passive"))
    )
    (net (code "39") (name "Net-(D5-PadA)") (class "Default")
      (node (ref "D5") (pin "A") (pinfunction "A_A") (pintype "passive"))
      (node (ref "R37") (pin "2") (pinfunction "2_2") (pintype "passive"))
    )
    (net (code "40") (name "Net-(D6-PadA)") (class "Default")
      (node (ref "D6") (pin "A") (pinfunction "A_A") (pintype "passive"))
      (node (ref "D9") (pin "2") (pinfunction "A_2") (pintype "passive"))
    )
    (net (code "41") (name "Net-(D6-PadK)") (class "Default")
      (node (ref "D6") (pin "K") (pinfunction "K_K") (pintype "passive"))
      (node (ref "R38") (pin "1") (pinfunction "1_1") (pintype "passive"))
    )
    (net (code "42") (name "Net-(D7-A-Pad1)") (class "Default")
      (node (ref "D7") (pin "1") (pinfunction "A_1") (pintype "passive"))
      (node (ref "R38") (pin "2") (pinfunction "2_2") (pintype "passive"))
    )
    (net (code "43") (name "Net-(D7-A-Pad2)") (class "Default")
      (node (ref "D7") (pin "2") (pinfunction "A_2") (pintype "passive"))
      (node (ref "R37") (pin "1") (pinfunction "1_1") (pintype "passive"))
    )
    (net (code "44") (name "Net-(D8-PadK)") (class "Default")
      (node (ref "D8") (pin "K") (pinfunction "K_K") (pintype "passive"))
      (node (ref "R39") (pin "1") (pinfunction "1_1") (pintype "passive"))
    )
    (net (code "45") (name "Net-(D9-A-Pad1)") (class "Default")
      (node (ref "D9") (pin "1") (pinfunction "A_1") (pintype "passive"))
      (node (ref "R39") (pin "2") (pinfunction "2_2") (pintype "passive"))
    )
    (net (code "46") (name "Net-(D11-A)") (class "Default")
      (node (ref "D11") (pin "1") (pinfunction "A_1") (pintype "passive"))
      (node (ref "Q21") (pin "1") (pinfunction "G_1") (pintype "passive"))
      (node (ref "R10") (pin "2") (pinfunction "2_2") (pintype "passive"))
      (node (ref "R31") (pin "2") (pinfunction "2_2") (pintype "passive"))
      (node (ref "R5") (pin "1") (pinfunction "1_1") (pintype "passive"))
    )
    (net (code "47") (name "Net-(D13-PadK)") (class "Default")
      (node (ref "D13") (pin "K") (pinfunction "K_K") (pintype "passive"))
      (node (ref "R11") (pin "2") (pinfunction "2_2") (pintype "passive"))
    )
    (net (code "48") (name "Net-(Q1-DRAIN1)") (class "Default")
      (node (ref "Q1") (pin "5") (pinfunction "DRAIN1_5") (pintype "passive"))
      (node (ref "Q1") (pin "6") (pinfunction "DRAIN2_6") (pintype "passive"))
      (node (ref "Q1") (pin "7") (pinfunction "DRAIN3_7") (pintype "passive"))
      (node (ref "Q1") (pin "8") (pinfunction "DRAIN4_8") (pintype "passive"))
      (node (ref "Q16") (pin "5") (pinfunction "DRAIN1_5") (pintype "passive"))
      (node (ref "Q16") (pin "6") (pinfunction "DRAIN2_6") (pintype "passive"))
      (node (ref "Q16") (pin "7") (pinfunction "DRAIN3_7") (pintype "passive"))
      (node (ref "Q16") (pin "8") (pinfunction "DRAIN4_8") (pintype "passive"))
      (node (ref "Q18") (pin "5") (pinfunction "DRAIN1_5") (pintype "passive"))
      (node (ref "Q18") (pin "6") (pinfunction "DRAIN2_6") (pintype "passive"))
      (node (ref "Q18") (pin "7") (pinfunction "DRAIN3_7") (pintype "passive"))
      (node (ref "Q18") (pin "8") (pinfunction "DRAIN4_8") (pintype "passive"))
      (node (ref "Q19") (pin "5") (pinfunction "DRAIN1_5") (pintype "passive"))
      (node (ref "Q19") (pin "6") (pinfunction "DRAIN2_6") (pintype "passive"))
      (node (ref "Q19") (pin "7") (pinfunction "DRAIN3_7") (pintype "passive"))
      (node (ref "Q19") (pin "8") (pinfunction "DRAIN4_8") (pintype "passive"))
      (node (ref "Q2") (pin "5") (pinfunction "DRAIN1_5") (pintype "passive"))
      (node (ref "Q2") (pin "6") (pinfunction "DRAIN2_6") (pintype "passive"))
      (node (ref "Q2") (pin "7") (pinfunction "DRAIN3_7") (pintype "passive"))
      (node (ref "Q2") (pin "8") (pinfunction "DRAIN4_8") (pintype "passive"))
      (node (ref "Q20") (pin "5") (pinfunction "DRAIN1_5") (pintype "passive"))
      (node (ref "Q20") (pin "6") (pinfunction "DRAIN2_6") (pintype "passive"))
      (node (ref "Q20") (pin "7") (pinfunction "DRAIN3_7") (pintype "passive"))
      (node (ref "Q20") (pin "8") (pinfunction "DRAIN4_8") (pintype "passive"))
      (node (ref "Q3") (pin "5") (pinfunction "DRAIN1_5") (pintype "passive"))
      (node (ref "Q3") (pin "6") (pinfunction "DRAIN2_6") (pintype "passive"))
      (node (ref "Q3") (pin "7") (pinfunction "DRAIN3_7") (pintype "passive"))
      (node (ref "Q3") (pin "8") (pinfunction "DRAIN4_8") (pintype "passive"))
      (node (ref "Q4") (pin "5") (pinfunction "DRAIN1_5") (pintype "passive"))
      (node (ref "Q4") (pin "6") (pinfunction "DRAIN2_6") (pintype "passive"))
      (node (ref "Q4") (pin "7") (pinfunction "DRAIN3_7") (pintype "passive"))
      (node (ref "Q4") (pin "8") (pinfunction "DRAIN4_8") (pintype "passive"))
      (node (ref "Q5") (pin "5") (pinfunction "DRAIN1_5") (pintype "passive"))
      (node (ref "Q5") (pin "6") (pinfunction "DRAIN2_6") (pintype "passive"))
      (node (ref "Q5") (pin "7") (pinfunction "DRAIN3_7") (pintype "passive"))
      (node (ref "Q5") (pin "8") (pinfunction "DRAIN4_8") (pintype "passive"))
      (node (ref "Q6") (pin "5") (pinfunction "DRAIN1_5") (pintype "passive"))
      (node (ref "Q6") (pin "6") (pinfunction "DRAIN2_6") (pintype "passive"))
      (node (ref "Q6") (pin "7") (pinfunction "DRAIN3_7") (pintype "passive"))
      (node (ref "Q6") (pin "8") (pinfunction "DRAIN4_8") (pintype "passive"))
    )
    (net (code "49") (name "Net-(Q7-S1)") (class "Default")
      (node (ref "Q7") (pin "1") (pinfunction "S1_1") (pintype "passive"))
      (node (ref "Q7") (pin "3") (pinfunction "S2_3") (pintype "passive"))
      (node (ref "R21") (pin "2") (pinfunction "2_2") (pintype "passive"))
    )
    (net (code "50") (name "Net-(Q8-S1)") (class "Default")
      (node (ref "Q8") (pin "1") (pinfunction "S1_1") (pintype "passive"))
      (node (ref "Q8") (pin "3") (pinfunction "S2_3") (pintype "passive"))
      (node (ref "R16") (pin "2") (pinfunction "2_2") (pintype "passive"))
    )
    (net (code "51") (name "Net-(Q10-D)") (class "Default")
      (node (ref "Q10") (pin "3") (pinfunction "D_3") (pintype "passive"))
      (node (ref "Q8") (pin "2") (pinfunction "G1_2") (pintype "passive"))
      (node (ref "Q8") (pin "4") (pinfunction "G2_4") (pintype "passive"))
      (node (ref "R16") (pin "1") (pinfunction "1_1") (pintype "passive"))
    )
    (net (code "52") (name "Net-(Q11-D)") (class "Default")
      (node (ref "Q11") (pin "3") (pinfunction "D_3") (pintype "passive"))
      (node (ref "Q7") (pin "2") (pinfunction "G1_2") (pintype "passive"))
      (node (ref "Q7") (pin "4") (pinfunction "G2_4") (pintype "passive"))
      (node (ref "R21") (pin "1") (pinfunction "1_1") (pintype "passive"))
    )
    (net (code "53") (name "Net-(Q13-G1)") (class "Default")
      (node (ref "Q13") (pin "2") (pinfunction "G1_2") (pintype "passive"))
      (node (ref "Q13") (pin "4") (pinfunction "G2_4") (pintype "passive"))
      (node (ref "Q14") (pin "3") (pinfunction "D_3") (pintype "passive"))
      (node (ref "R26") (pin "1") (pinfunction "1_1") (pintype "passive"))
    )
    (net (code "54") (name "Net-(Q13-S1)") (class "Default")
      (node (ref "Q13") (pin "1") (pinfunction "S1_1") (pintype "passive"))
      (node (ref "Q13") (pin "3") (pinfunction "S2_3") (pintype "passive"))
      (node (ref "R26") (pin "2") (pinfunction "2_2") (pintype "passive"))
    )
    (net (code "55") (name "Net-(U2A-1A)") (class "Default")
      (node (ref "C12") (pin "1") (pinfunction "1_1") (pintype "passive"))
      (node (ref "R7") (pin "1") (pinfunction "1_1") (pintype "passive"))
      (node (ref "U2") (pin "1") (pinfunction "1A_1") (pintype "input"))
    )
    (net (code "56") (name "Net-(U2A-1Y)") (class "Default")
      (node (ref "C14") (pin "1") (pinfunction "1_1") (pintype "passive"))
      (node (ref "D13") (pin "A") (pinfunction "A_A") (pintype "passive"))
      (node (ref "R7") (pin "2") (pinfunction "2_2") (pintype "passive"))
      (node (ref "U2") (pin "3") (pinfunction "2A_3") (pintype "input"))
      (node (ref "U2") (pin "6") (pinfunction "1Y_6") (pintype "output"))
    )
    (net (code "57") (name "Net-(U2B-2Y)") (class "Default")
      (node (ref "LS1") (pin "1") (pinfunction "1_1") (pintype "passive"))
      (node (ref "LS1") (pin "1A") (pinfunction "1A_1A") (pintype "passive"))
      (node (ref "R11") (pin "1") (pinfunction "1_1") (pintype "passive"))
      (node (ref "U2") (pin "4") (pinfunction "2Y_4") (pintype "output"))
    )
    (net (code "58") (name "P-") (class "Default")
      (node (ref "Q16") (pin "1") (pinfunction "SOURCE1_1") (pintype "passive"))
      (node (ref "Q16") (pin "2") (pinfunction "SOURCE2_2") (pintype "passive"))
      (node (ref "Q16") (pin "3") (pinfunction "SOURCE3_3") (pintype "passive"))
      (node (ref "Q16") (pin "4") (pinfunction "SOURCE4_4") (pintype "passive"))
      (node (ref "Q17") (pin "3") (pinfunction "D_3") (pintype "passive"))
      (node (ref "Q19") (pin "1") (pinfunction "SOURCE1_1") (pintype "passive"))
      (node (ref "Q19") (pin "2") (pinfunction "SOURCE2_2") (pintype "passive"))
      (node (ref "Q19") (pin "3") (pinfunction "SOURCE3_3") (pintype "passive"))
      (node (ref "Q19") (pin "4") (pinfunction "SOURCE4_4") (pintype "passive"))
      (node (ref "Q2") (pin "1") (pinfunction "SOURCE1_1") (pintype "passive"))
      (node (ref "Q2") (pin "2") (pinfunction "SOURCE2_2") (pintype "passive"))
      (node (ref "Q2") (pin "3") (pinfunction "SOURCE3_3") (pintype "passive"))
      (node (ref "Q2") (pin "4") (pinfunction "SOURCE4_4") (pintype "passive"))
      (node (ref "Q3") (pin "1") (pinfunction "SOURCE1_1") (pintype "passive"))
      (node (ref "Q3") (pin "2") (pinfunction "SOURCE2_2") (pintype "passive"))
      (node (ref "Q3") (pin "3") (pinfunction "SOURCE3_3") (pintype "passive"))
      (node (ref "Q3") (pin "4") (pinfunction "SOURCE4_4") (pintype "passive"))
      (node (ref "Q5") (pin "1") (pinfunction "SOURCE1_1") (pintype "passive"))
      (node (ref "Q5") (pin "2") (pinfunction "SOURCE2_2") (pintype "passive"))
      (node (ref "Q5") (pin "3") (pinfunction "SOURCE3_3") (pintype "passive"))
      (node (ref "Q5") (pin "4") (pinfunction "SOURCE4_4") (pintype "passive"))
      (node (ref "R15") (pin "2") (pinfunction "2_2") (pintype "passive"))
      (node (ref "R41") (pin "2") (pinfunction "2_2") (pintype "passive"))
      (node (ref "R42") (pin "2") (pinfunction "2_2") (pintype "passive"))
      (node (ref "R9") (pin "2") (pinfunction "2_2") (pintype "passive"))
    )
    (net (code "59") (name "VGND") (class "Default")
      (node (ref "C10") (pin "1") (pinfunction "1_1") (pintype "passive"))
      (node (ref "C11") (pin "1") (pinfunction "1_1") (pintype "passive"))
      (node (ref "C12") (pin "2") (pinfunction "2_2") (pintype "passive"))
      (node (ref "C13") (pin "2") (pinfunction "2_2") (pintype "passive"))
      (node (ref "D12") (pin "1") (pinfunction "A_1") (pintype "passive"))
      (node (ref "U2") (pin "2") (pinfunction "GND_2") (pintype "power_in"))
      (node (ref "VR1") (pin "1") (pinfunction "GND_1") (pintype "passive"))
    )
    (net (code "60") (name "unconnected-(U1A-BALDN-Pad13)") (class "Default")
      (node (ref "U1") (pin "13") (pinfunction "BALDN_13") (pintype "passive+no_connect"))
    )
    (net (code "61") (name "unconnected-(U1A-BALUP-Pad1)") (class "Default")
      (node (ref "U1") (pin "1") (pinfunction "BALUP_1") (pintype "output+no_connect"))
    )
    (net (code "62") (name "unconnected-(U1A-OCCT-Pad15)") (class "Default")
      (node (ref "U1") (pin "15") (pinfunction "OCCT_15") (pintype "passive+no_connect"))
    )
    (net (code "63") (name "unconnected-(U1C-BAL1-Pad18)") (class "Default")
      (node (ref "U1") (pin "18") (pinfunction "BAL1_18") (pintype "power_in+no_connect"))
    )
    (net (code "64") (name "unconnected-(U1C-BAL2-Pad20)") (class "Default")
      (node (ref "U1") (pin "20") (pinfunction "BAL2_20") (pintype "power_in+no_connect"))
    )
  )
)
